# 05_RS232_USB.net
KiCad netlist of a schematic drawn in Altium Designer
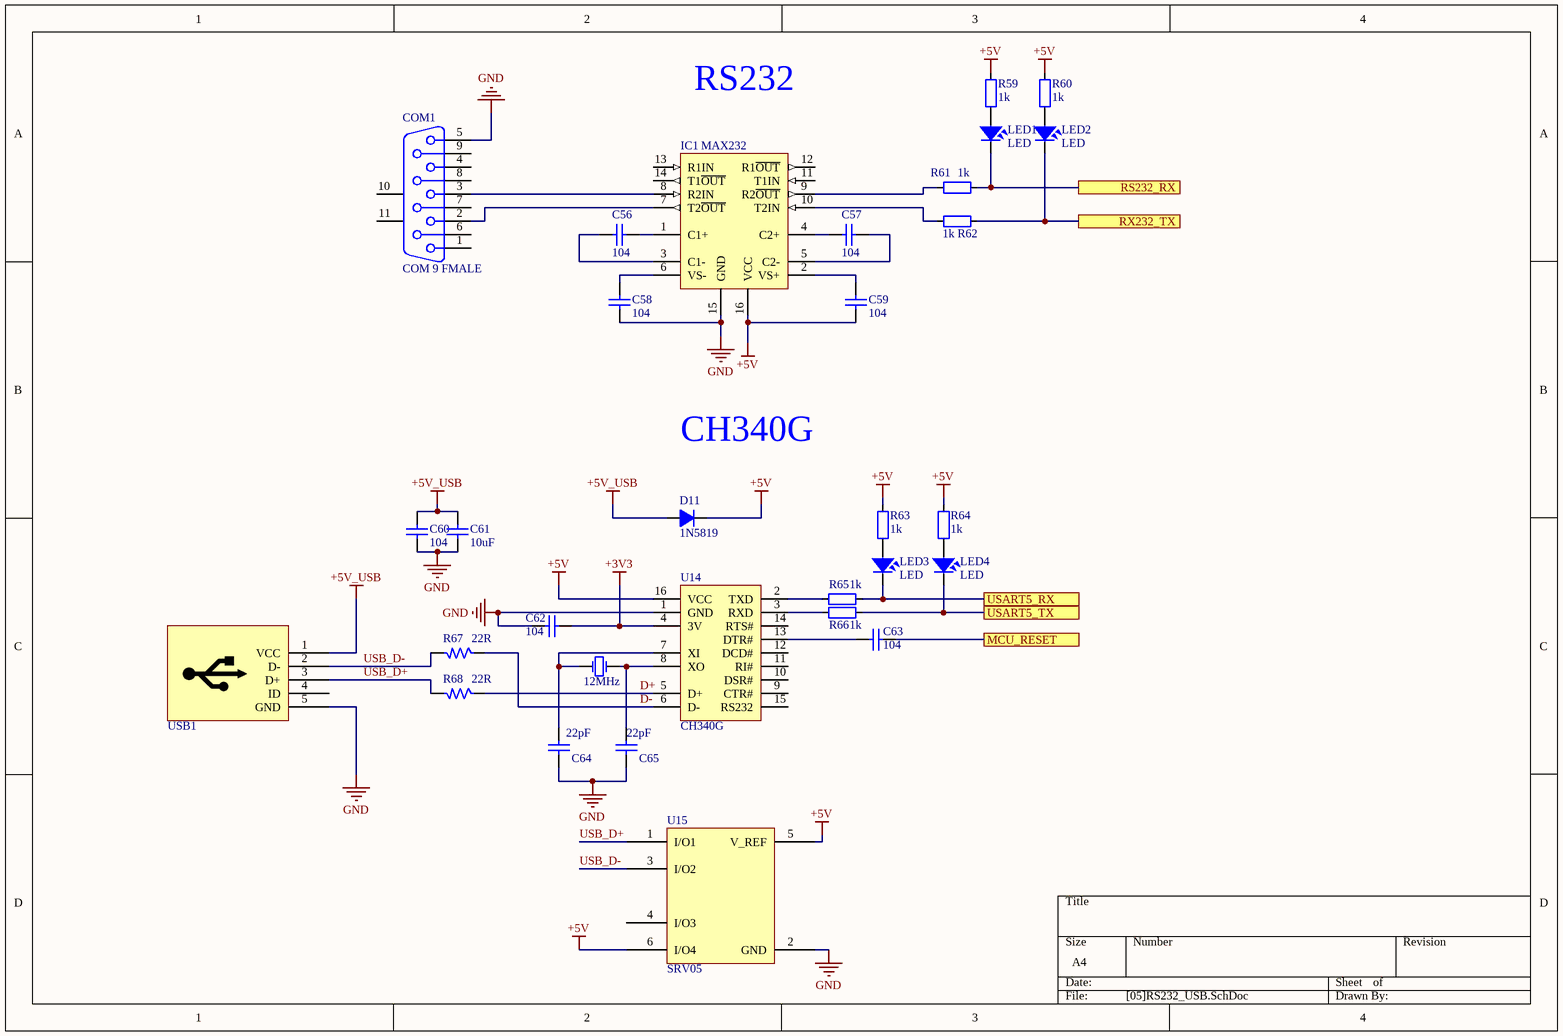
[diagram p0: [05]RS232_USB.SchDoc]

(export (version "E")
  (design (tool "Eeschema 10.0.6"))
  (components
    (comp (ref "C56")
      (value "104")
      (footprint "CAP_0603")
      (description "Capacitor")
      (fields (field (name "PUBLISHER") "Altium Limited"))
      (libsource (lib "My Library") (part "CapSMD"))
    )
    (comp (ref "C57")
      (value "104")
      (footprint "CAP_0603")
      (description "Capacitor")
      (fields (field (name "PUBLISHER") "Altium Limited"))
      (libsource (lib "My Library") (part "CapSMD"))
    )
    (comp (ref "C58")
      (value "104")
      (footprint "CAP_0603")
      (description "Capacitor")
      (fields (field (name "PUBLISHER") "Altium Limited"))
      (libsource (lib "My Library") (part "CapSMD"))
    )
    (comp (ref "C59")
      (value "104")
      (footprint "CAP_0603")
      (description "Capacitor")
      (fields (field (name "PUBLISHER") "Altium Limited"))
      (libsource (lib "My Library") (part "CapSMD"))
    )
    (comp (ref "C60")
      (value "104")
      (footprint "CAP_0603")
      (description "Capacitor")
      (fields (field (name "PUBLISHER") "Altium Limited"))
      (libsource (lib "My Library") (part "CapSMD"))
    )
    (comp (ref "C61")
      (value "10uF")
      (footprint "CAP_0603")
      (description "Capacitor")
      (fields (field (name "PUBLISHER") "Altium Limited"))
      (libsource (lib "My Library") (part "CapSMD"))
    )
    (comp (ref "C62")
      (value "104")
      (footprint "CAP_0603")
      (description "Capacitor")
      (fields (field (name "PUBLISHER") "Altium Limited"))
      (libsource (lib "My Library") (part "CapSMD"))
    )
    (comp (ref "C63")
      (value "104")
      (footprint "CAP_0603")
      (description "Capacitor")
      (fields (field (name "PUBLISHER") "Altium Limited"))
      (libsource (lib "My Library") (part "CapSMD"))
    )
    (comp (ref "C64")
      (value "22pF")
      (footprint "CAP_0603")
      (description "Capacitor")
      (fields (field (name "PUBLISHER") "Altium Limited"))
      (libsource (lib "My Library") (part "CapSMD"))
    )
    (comp (ref "C65")
      (value "22pF")
      (footprint "CAP_0603")
      (description "Capacitor")
      (fields (field (name "PUBLISHER") "Altium Limited"))
      (libsource (lib "My Library") (part "CapSMD"))
    )
    (comp (ref "COM1")
      (value "COM 9 FMALE")
      (footprint "DSB 9-F")
      (description "COM 9")
      (fields (field (name "PUBLISHER") "Altium Limited"))
      (libsource (lib "syhaunguyen") (part "DSB9F"))
    )
    (comp (ref "D11")
      (value "1N5819")
      (footprint "DO-214AB SMA")
      (description "Diode 1A")
      (libsource (lib "GPS_Traking_V1_1") (part "D1A_1"))
    )
    (comp (ref "IC1")
      (value "MAX232")
      (footprint "MAX232DR")
      (description "Dual EIA-232 Driver/Receiver")
      (libsource (lib "My Library") (part "MAX232"))
    )
    (comp (ref "LED1")
      (value "LED")
      (footprint "LED-0805-Green")
      (description "LED Single colour Green and Red")
      (libsource (lib "My Library") (part "LED"))
    )
    (comp (ref "LED2")
      (value "LED")
      (footprint "LED-0805-Green")
      (description "LED Single colour Green and Red")
      (libsource (lib "My Library") (part "LED"))
    )
    (comp (ref "LED3")
      (value "LED")
      (footprint "LED-0805-Green")
      (description "LED Single colour Green and Red")
      (libsource (lib "My Library") (part "LED"))
    )
    (comp (ref "LED4")
      (value "LED")
      (footprint "LED-0805-Green")
      (description "LED Single colour Green and Red")
      (libsource (lib "My Library") (part "LED"))
    )
    (comp (ref "R59")
      (value "1k")
      (footprint "RES-SMD-0603")
      (description "Resistor")
      (fields
        (field (name "MANUFACTURER") "Generic Components")
        (field (name "PUBLISHER") "Altium Hobart Technology Centre")
      )
      (libsource (lib "My Library") (part "Resistor - SMD"))
    )
    (comp (ref "R60")
      (value "1k")
      (footprint "RES-SMD-0603")
      (description "Resistor")
      (fields
        (field (name "MANUFACTURER") "Generic Components")
        (field (name "PUBLISHER") "Altium Hobart Technology Centre")
      )
      (libsource (lib "My Library") (part "Resistor - SMD"))
    )
    (comp (ref "R61")
      (value "1k")
      (footprint "RES-SMD-0603")
      (description "Resistor")
      (fields
        (field (name "MANUFACTURER") "Generic Components")
        (field (name "PUBLISHER") "Altium Hobart Technology Centre")
      )
      (libsource (lib "My Library") (part "Resistor - SMD"))
    )
    (comp (ref "R62")
      (value "1k")
      (footprint "RES-SMD-0603")
      (description "Resistor")
      (fields
        (field (name "MANUFACTURER") "Generic Components")
        (field (name "PUBLISHER") "Altium Hobart Technology Centre")
      )
      (libsource (lib "My Library") (part "Resistor - SMD"))
    )
    (comp (ref "R63")
      (value "1k")
      (footprint "RES-SMD-0603")
      (description "Resistor")
      (fields
        (field (name "MANUFACTURER") "Generic Components")
        (field (name "PUBLISHER") "Altium Hobart Technology Centre")
      )
      (libsource (lib "My Library") (part "Resistor - SMD"))
    )
    (comp (ref "R64")
      (value "1k")
      (footprint "RES-SMD-0603")
      (description "Resistor")
      (fields
        (field (name "MANUFACTURER") "Generic Components")
        (field (name "PUBLISHER") "Altium Hobart Technology Centre")
      )
      (libsource (lib "My Library") (part "Resistor - SMD"))
    )
    (comp (ref "R65")
      (value "1k")
      (footprint "RES-SMD-0603")
      (description "Resistor")
      (fields
        (field (name "MANUFACTURER") "Generic Components")
        (field (name "PUBLISHER") "Altium Hobart Technology Centre")
      )
      (libsource (lib "My Library") (part "Resistor - SMD"))
    )
    (comp (ref "R66")
      (value "1k")
      (footprint "RES-SMD-0603")
      (description "Resistor")
      (fields
        (field (name "MANUFACTURER") "Generic Components")
        (field (name "PUBLISHER") "Altium Hobart Technology Centre")
      )
      (libsource (lib "My Library") (part "Resistor - SMD"))
    )
    (comp (ref "R67")
      (value "22R")
      (footprint "RES-SMD-0603")
      (description "Resistor SMD")
      (libsource (lib "GPS_Traking_V1_1") (part "RM"))
    )
    (comp (ref "R68")
      (value "22R")
      (footprint "RES-SMD-0603")
      (description "Resistor SMD")
      (libsource (lib "GPS_Traking_V1_1") (part "RM"))
    )
    (comp (ref "U14")
      (value "CH340G")
      (footprint "SO16")
      (description "High and Low Side Driver")
      (fields (field (name "PUBLISHER") "Altium Limited"))
      (libsource (lib "My Library") (part "CH340G"))
    )
    (comp (ref "U15")
      (value "SRV05")
      (footprint "SOT23-6")
      (description "TVS DIODE 5V")
      (libsource (lib "My Library") (part "SRV05"))
    )
    (comp (ref "USB1") (value "USB") (footprint "USB-B-Mini") (libsource (lib "My Library") (part "USB-M")))
    (comp (ref "Y2")
      (value "12MHz")
      (footprint "XTAL-5032")
      (description "Crystal Oscillator")
      (fields (field (name "PUBLISHER") "Altium Limited"))
      (libsource (lib "My Library") (part "XTAL"))
    )
  )
  (nets
    (net (code "1") (name "+3V3") (class "Default")
      (node (ref "C62") (pin "2") (pinfunction "2_2") (pintype "passive"))
      (node (ref "U14") (pin "4") (pinfunction "3V_4") (pintype "passive"))
    )
    (net (code "2") (name "+5V") (class "Default")
      (node (ref "C59") (pin "2") (pinfunction "2_2") (pintype "passive"))
      (node (ref "D11") (pin "2") (pinfunction "K_2") (pintype "passive"))
      (node (ref "IC1") (pin "16") (pinfunction "VCC_16") (pintype "power_in"))
      (node (ref "R59") (pin "2") (pinfunction "2_2") (pintype "passive"))
      (node (ref "R60") (pin "2") (pinfunction "2_2") (pintype "passive"))
      (node (ref "R63") (pin "2") (pinfunction "2_2") (pintype "passive"))
      (node (ref "R64") (pin "2") (pinfunction "2_2") (pintype "passive"))
      (node (ref "U14") (pin "16") (pinfunction "VCC_16") (pintype "passive"))
      (node (ref "U15") (pin "5") (pinfunction "V_REF_5") (pintype "passive"))
      (node (ref "U15") (pin "6") (pinfunction "I/O4_6") (pintype "passive"))
    )
    (net (code "3") (name "+5V_USB") (class "Default")
      (node (ref "C60") (pin "2") (pinfunction "2_2") (pintype "passive"))
      (node (ref "C61") (pin "2") (pinfunction "2_2") (pintype "passive"))
      (node (ref "D11") (pin "1") (pinfunction "A_1") (pintype "passive"))
      (node (ref "USB1") (pin "1") (pinfunction "VCC_1") (pintype "passive"))
    )
    (net (code "4") (name "/D+") (class "Default")
      (node (ref "R68") (pin "1") (pinfunction "1_1") (pintype "passive"))
      (node (ref "U14") (pin "5") (pinfunction "D+_5") (pintype "passive"))
    )
    (net (code "5") (name "/D-") (class "Default")
      (node (ref "R67") (pin "1") (pinfunction "1_1") (pintype "passive"))
      (node (ref "U14") (pin "6") (pinfunction "D-_6") (pintype "passive"))
    )
    (net (code "6") (name "/MCU_RESET") (class "Default")
      (node (ref "C63") (pin "2") (pinfunction "2_2") (pintype "passive"))
    )
    (net (code "7") (name "/RS232_RX") (class "Default")
      (node (ref "LED1") (pin "2") (pinfunction "2_2") (pintype "passive"))
      (node (ref "R61") (pin "1") (pinfunction "1_1") (pintype "passive"))
    )
    (net (code "8") (name "/RX232_TX") (class "Default")
      (node (ref "LED2") (pin "2") (pinfunction "2_2") (pintype "passive"))
      (node (ref "R62") (pin "1") (pinfunction "1_1") (pintype "passive"))
    )
    (net (code "9") (name "/USART5_RX") (class "Default")
      (node (ref "LED3") (pin "2") (pinfunction "2_2") (pintype "passive"))
      (node (ref "R65") (pin "2") (pinfunction "2_2") (pintype "passive"))
    )
    (net (code "10") (name "/USART5_TX") (class "Default")
      (node (ref "LED4") (pin "2") (pinfunction "2_2") (pintype "passive"))
      (node (ref "R66") (pin "2") (pinfunction "2_2") (pintype "passive"))
    )
    (net (code "11") (name "/USB_D+") (class "Default")
      (node (ref "R68") (pin "2") (pinfunction "2_2") (pintype "passive"))
      (node (ref "U15") (pin "1") (pinfunction "I/O1_1") (pintype "passive"))
      (node (ref "USB1") (pin "3") (pinfunction "D+_3") (pintype "passive"))
    )
    (net (code "12") (name "/USB_D-") (class "Default")
      (node (ref "R67") (pin "2") (pinfunction "2_2") (pintype "passive"))
      (node (ref "U15") (pin "3") (pinfunction "I/O2_3") (pintype "passive"))
      (node (ref "USB1") (pin "2") (pinfunction "D-_2") (pintype "passive"))
    )
    (net (code "13") (name "GND") (class "Default")
      (node (ref "C58") (pin "2") (pinfunction "2_2") (pintype "passive"))
      (node (ref "C60") (pin "1") (pinfunction "1_1") (pintype "passive"))
      (node (ref "C61") (pin "1") (pinfunction "1_1") (pintype "passive"))
      (node (ref "C62") (pin "1") (pinfunction "1_1") (pintype "passive"))
      (node (ref "C64") (pin "2") (pinfunction "2_2") (pintype "passive"))
      (node (ref "C65") (pin "2") (pinfunction "2_2") (pintype "passive"))
      (node (ref "COM1") (pin "5") (pinfunction "5_5") (pintype "passive"))
      (node (ref "IC1") (pin "15") (pinfunction "GND_15") (pintype "power_in"))
      (node (ref "U14") (pin "1") (pinfunction "GND_1") (pintype "passive"))
      (node (ref "U15") (pin "2") (pinfunction "GND_2") (pintype "passive"))
      (node (ref "USB1") (pin "5") (pinfunction "GND_5") (pintype "passive"))
    )
    (net (code "14") (name "Net-(IC1-C1+)") (class "Default")
      (node (ref "C56") (pin "1") (pinfunction "1_1") (pintype "passive"))
      (node (ref "IC1") (pin "1") (pinfunction "C1+_1") (pintype "passive"))
    )
    (net (code "15") (name "Net-(IC1-C1-)") (class "Default")
      (node (ref "C56") (pin "2") (pinfunction "2_2") (pintype "passive"))
      (node (ref "IC1") (pin "3") (pinfunction "C1-_3") (pintype "passive"))
    )
    (net (code "16") (name "Net-(IC1-C2+)") (class "Default")
      (node (ref "C57") (pin "2") (pinfunction "2_2") (pintype "passive"))
      (node (ref "IC1") (pin "4") (pinfunction "C2+_4") (pintype "passive"))
    )
    (net (code "17") (name "Net-(IC1-C2-)") (class "Default")
      (node (ref "C57") (pin "1") (pinfunction "1_1") (pintype "passive"))
      (node (ref "IC1") (pin "5") (pinfunction "C2-_5") (pintype "passive"))
    )
    (net (code "18") (name "Net-(IC1-R2IN)") (class "Default")
      (node (ref "COM1") (pin "3") (pinfunction "3_3") (pintype "passive"))
      (node (ref "IC1") (pin "8") (pinfunction "R2IN_8") (pintype "input"))
    )
    (net (code "19") (name "Net-(IC1-R2~{OUT})") (class "Default")
      (node (ref "IC1") (pin "9") (pinfunction "R2~{OUT}_9") (pintype "output"))
      (node (ref "R61") (pin "2") (pinfunction "2_2") (pintype "passive"))
    )
    (net (code "20") (name "Net-(IC1-T2IN)") (class "Default")
      (node (ref "IC1") (pin "10") (pinfunction "T2IN_10") (pintype "input"))
      (node (ref "R62") (pin "2") (pinfunction "2_2") (pintype "passive"))
    )
    (net (code "21") (name "Net-(IC1-T2~{OUT})") (class "Default")
      (node (ref "COM1") (pin "2") (pinfunction "2_2") (pintype "passive"))
      (node (ref "IC1") (pin "7") (pinfunction "T2~{OUT}_7") (pintype "output"))
    )
    (net (code "22") (name "Net-(IC1-VS+)") (class "Default")
      (node (ref "C59") (pin "1") (pinfunction "1_1") (pintype "passive"))
      (node (ref "IC1") (pin "2") (pinfunction "VS+_2") (pintype "power_in"))
    )
    (net (code "23") (name "Net-(IC1-VS-)") (class "Default")
      (node (ref "C58") (pin "1") (pinfunction "1_1") (pintype "passive"))
      (node (ref "IC1") (pin "6") (pinfunction "VS-_6") (pintype "power_in"))
    )
    (net (code "24") (name "Net-(LED1-Pad1)") (class "Default")
      (node (ref "LED1") (pin "1") (pinfunction "1_1") (pintype "passive"))
      (node (ref "R59") (pin "1") (pinfunction "1_1") (pintype "passive"))
    )
    (net (code "25") (name "Net-(LED2-Pad1)") (class "Default")
      (node (ref "LED2") (pin "1") (pinfunction "1_1") (pintype "passive"))
      (node (ref "R60") (pin "1") (pinfunction "1_1") (pintype "passive"))
    )
    (net (code "26") (name "Net-(LED3-Pad1)") (class "Default")
      (node (ref "LED3") (pin "1") (pinfunction "1_1") (pintype "passive"))
      (node (ref "R63") (pin "1") (pinfunction "1_1") (pintype "passive"))
    )
    (net (code "27") (name "Net-(LED4-Pad1)") (class "Default")
      (node (ref "LED4") (pin "1") (pinfunction "1_1") (pintype "passive"))
      (node (ref "R64") (pin "1") (pinfunction "1_1") (pintype "passive"))
    )
    (net (code "28") (name "Net-(U14-DTR#)") (class "Default")
      (node (ref "C63") (pin "1") (pinfunction "1_1") (pintype "passive"))
      (node (ref "U14") (pin "13") (pinfunction "DTR#_13") (pintype "passive"))
    )
    (net (code "29") (name "Net-(U14-RXD)") (class "Default")
      (node (ref "R66") (pin "1") (pinfunction "1_1") (pintype "passive"))
      (node (ref "U14") (pin "3") (pinfunction "RXD_3") (pintype "passive"))
    )
    (net (code "30") (name "Net-(U14-TXD)") (class "Default")
      (node (ref "R65") (pin "1") (pinfunction "1_1") (pintype "passive"))
      (node (ref "U14") (pin "2") (pinfunction "TXD_2") (pintype "passive"))
    )
    (net (code "31") (name "Net-(U14-XI)") (class "Default")
      (node (ref "C64") (pin "1") (pinfunction "1_1") (pintype "passive"))
      (node (ref "U14") (pin "7") (pinfunction "XI_7") (pintype "passive"))
      (node (ref "Y2") (pin "1") (pinfunction "OSC1_1") (pintype "passive"))
    )
    (net (code "32") (name "Net-(U14-XO)") (class "Default")
      (node (ref "C65") (pin "1") (pinfunction "1_1") (pintype "passive"))
      (node (ref "U14") (pin "8") (pinfunction "XO_8") (pintype "passive"))
      (node (ref "Y2") (pin "2") (pinfunction "OSC2_2") (pintype "passive"))
    )
    (net (code "33") (name "unconnected-(COM1-MH1-Pad10)") (class "Default")
      (node (ref "COM1") (pin "10") (pinfunction "MH1_10") (pintype "passive"))
    )
    (net (code "34") (name "unconnected-(COM1-MH2-Pad11)") (class "Default")
      (node (ref "COM1") (pin "11") (pinfunction "MH2_11") (pintype "passive"))
    )
    (net (code "35") (name "unconnected-(COM1-Pad1)") (class "Default")
      (node (ref "COM1") (pin "1") (pinfunction "1_1") (pintype "passive"))
    )
    (net (code "36") (name "unconnected-(COM1-Pad4)") (class "Default")
      (node (ref "COM1") (pin "4") (pinfunction "4_4") (pintype "passive"))
    )
    (net (code "37") (name "unconnected-(COM1-Pad6)") (class "Default")
      (node (ref "COM1") (pin "6") (pinfunction "6_6") (pintype "passive"))
    )
    (net (code "38") (name "unconnected-(COM1-Pad7)") (class "Default")
      (node (ref "COM1") (pin "7") (pinfunction "7_7") (pintype "passive"))
    )
    (net (code "39") (name "unconnected-(COM1-Pad8)") (class "Default")
      (node (ref "COM1") (pin "8") (pinfunction "8_8") (pintype "passive"))
    )
    (net (code "40") (name "unconnected-(COM1-Pad9)") (class "Default")
      (node (ref "COM1") (pin "9") (pinfunction "9_9") (pintype "passive"))
    )
    (net (code "41") (name "unconnected-(IC1-R1IN-Pad13)") (class "Default")
      (node (ref "IC1") (pin "13") (pinfunction "R1IN_13") (pintype "input"))
    )
    (net (code "42") (name "unconnected-(IC1-R1~{OUT}-Pad12)") (class "Default")
      (node (ref "IC1") (pin "12") (pinfunction "R1~{OUT}_12") (pintype "output"))
    )
    (net (code "43") (name "unconnected-(IC1-T1IN-Pad11)") (class "Default")
      (node (ref "IC1") (pin "11") (pinfunction "T1IN_11") (pintype "input"))
    )
    (net (code "44") (name "unconnected-(IC1-T1~{OUT}-Pad14)") (class "Default")
      (node (ref "IC1") (pin "14") (pinfunction "T1~{OUT}_14") (pintype "output"))
    )
    (net (code "45") (name "unconnected-(U14-CTR#-Pad9)") (class "Default")
      (node (ref "U14") (pin "9") (pinfunction "CTR#_9") (pintype "passive"))
    )
    (net (code "46") (name "unconnected-(U14-DCD#-Pad12)") (class "Default")
      (node (ref "U14") (pin "12") (pinfunction "DCD#_12") (pintype "passive"))
    )
    (net (code "47") (name "unconnected-(U14-DSR#-Pad10)") (class "Default")
      (node (ref "U14") (pin "10") (pinfunction "DSR#_10") (pintype "passive"))
    )
    (net (code "48") (name "unconnected-(U14-RI#-Pad11)") (class "Default")
      (node (ref "U14") (pin "11") (pinfunction "RI#_11") (pintype "passive"))
    )
    (net (code "49") (name "unconnected-(U14-RS232-Pad15)") (class "Default")
      (node (ref "U14") (pin "15") (pinfunction "RS232_15") (pintype "passive"))
    )
    (net (code "50") (name "unconnected-(U14-RTS#-Pad14)") (class "Default")
      (node (ref "U14") (pin "14") (pinfunction "RTS#_14") (pintype "passive"))
    )
    (net (code "51") (name "unconnected-(U15-I{slash}O3-Pad4)") (class "Default")
      (node (ref "U15") (pin "4") (pinfunction "I/O3_4") (pintype "passive"))
    )
    (net (code "52") (name "unconnected-(USB1-ID-Pad4)") (class "Default")
      (node (ref "USB1") (pin "4") (pinfunction "ID_4") (pintype "passive"))
    )
  )
)
